# top.net
KiCad netlist of a schematic drawn in Altium Designer
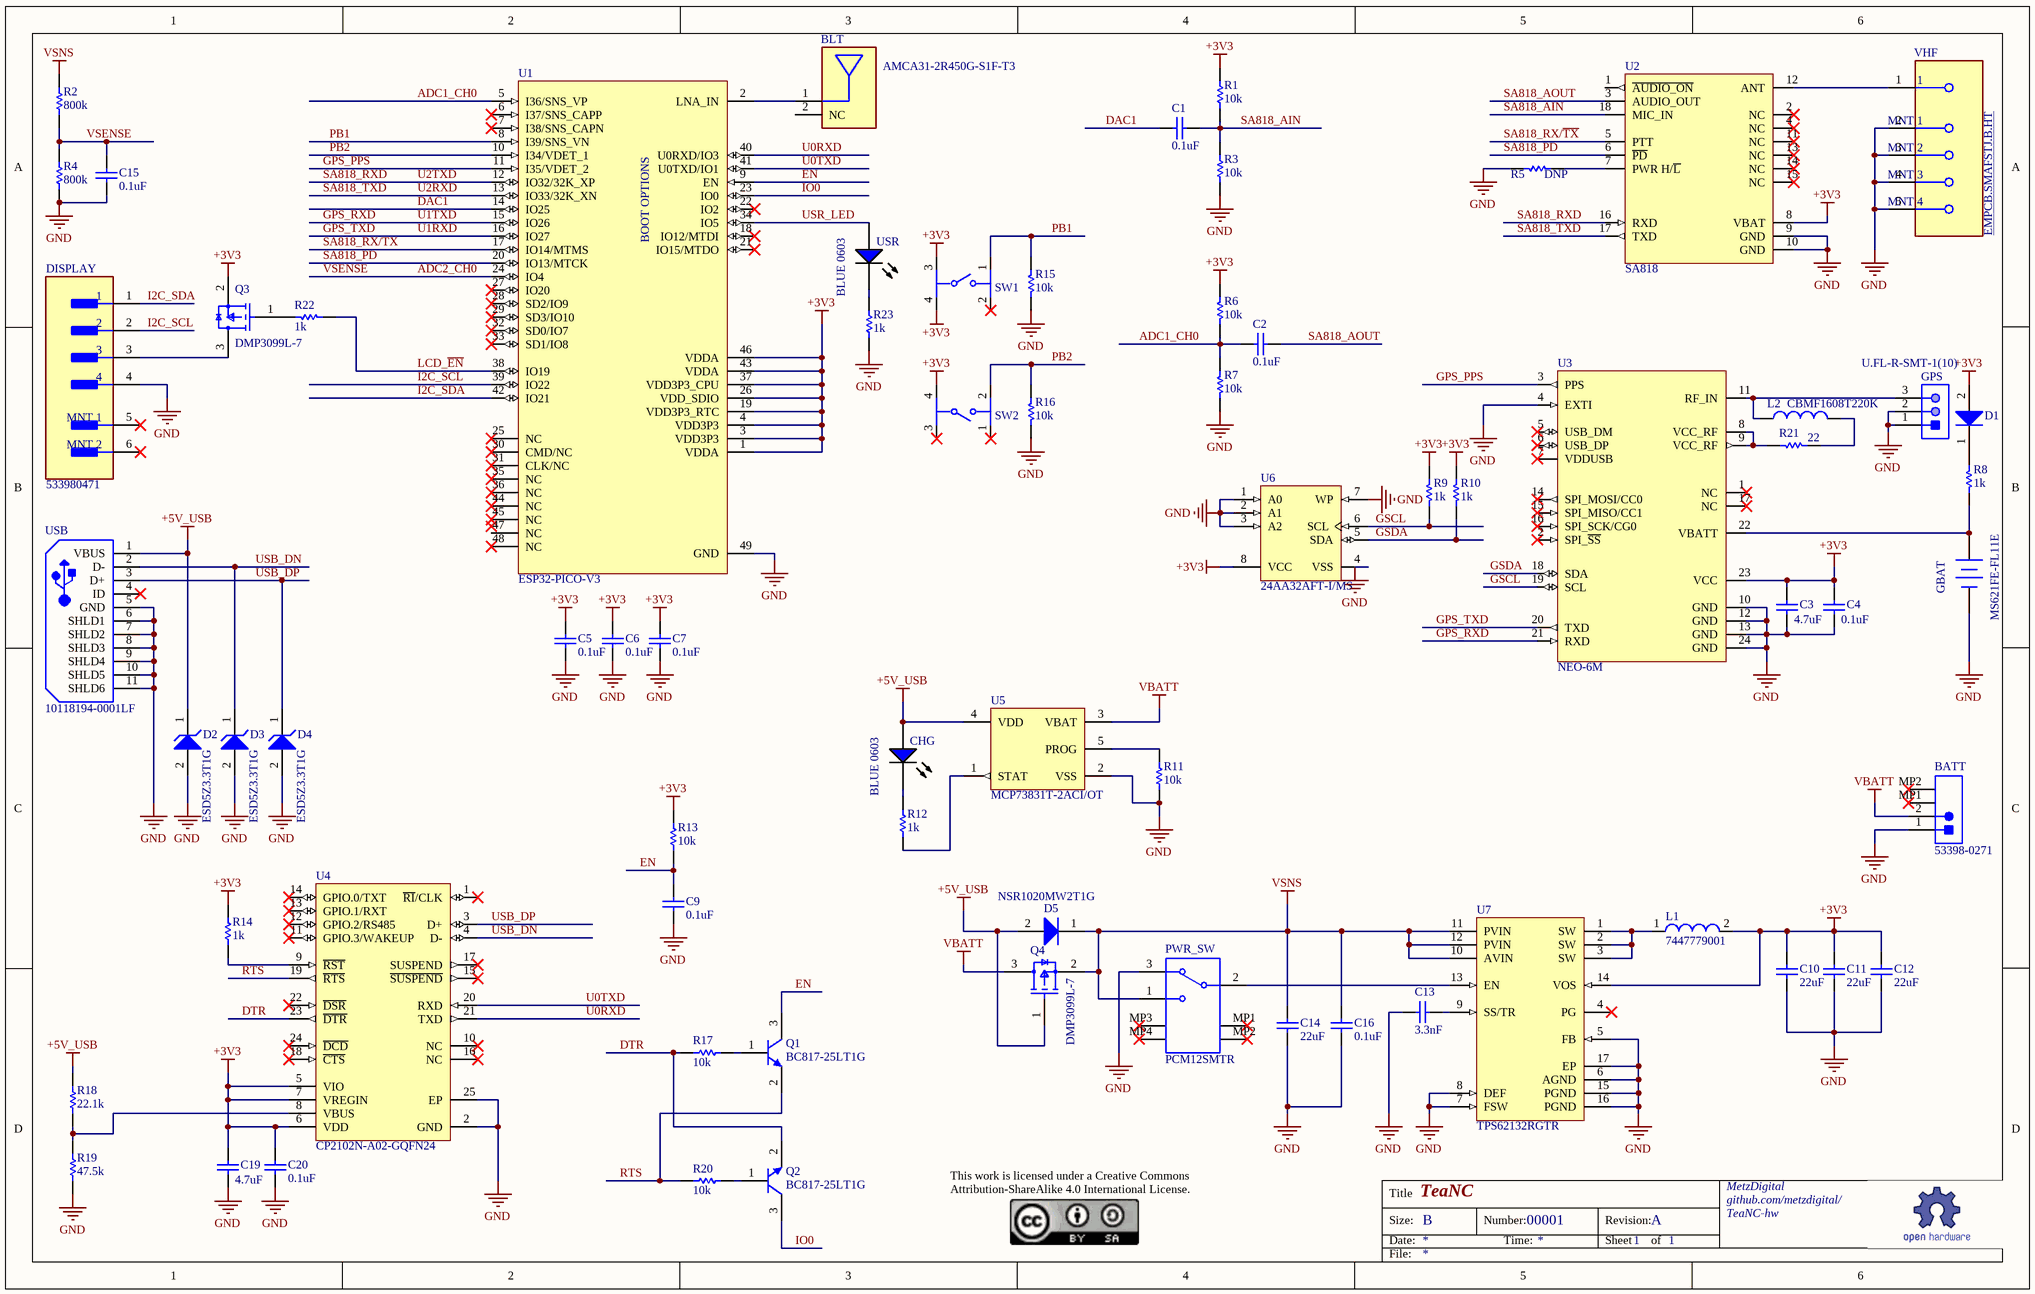
[diagram p0: top.SchDoc]

(export (version "E")
  (design (tool "Eeschema 10.0.6"))
  (components
    (comp (ref "BATT")
      (value "53398-0271")
      (footprint "MOLX-53398-0271_V")
      (description "Male Header, Pitch 1.25 mm, 1 x 2 Position, Height 4.7 mm, -40 to 85 degC, RoHS, Tape and Reel")
      (fields (field (name "MANUFACTURER") "Molex"))
      (libsource (lib "Altium Content Vault") (part "CN-1P-2M-R2"))
    )
    (comp (ref "BLT")
      (value "AMCA31-2R450G-S1F-T3")
      (footprint "FP-AMCA31-MFG")
      (description "RF ANT 2.4GHZ CHIP SOLDER SMD")
      (fields
        (field (name "OCTOPART") "https://octopart.com/amca31-2r450g-s1f-t3-abracon-31435383")
        (field (name "MANUFACTURER") "Abracon")
      )
      (libsource (lib "Altium Content Vault") (part "feefd54aed95757a858c12fc87bd8d5"))
    )
    (comp (ref "C1")
      (value "0.1uF")
      (footprint "CAPC0603(1608)100_M")
      (description "CAP 100nF 50V ±20% 0603 (1608 Metric) Thickness 1mm SMD")
      (fields (field (name "TOLERANCE") "Â±20%"))
      (libsource (lib "Altium Content Vault") (part "CMP-1035-02593-1"))
    )
    (comp (ref "C2")
      (value "0.1uF")
      (footprint "CAPC0603(1608)100_M")
      (description "CAP 100nF 50V ±20% 0603 (1608 Metric) Thickness 1mm SMD")
      (fields (field (name "TOLERANCE") "Â±20%"))
      (libsource (lib "Altium Content Vault") (part "CMP-1035-02593-1"))
    )
    (comp (ref "C3")
      (value "4.7uF")
      (footprint "CAPC0603(1608)100_M")
      (description "CAP 100nF 50V ±20% 0603 (1608 Metric) Thickness 1mm SMD")
      (fields (field (name "TOLERANCE") "Â±20%"))
      (libsource (lib "Altium Content Vault") (part "CMP-1035-02593-1"))
    )
    (comp (ref "C4")
      (value "0.1uF")
      (footprint "CAPC0603(1608)100_M")
      (description "CAP 100nF 50V ±20% 0603 (1608 Metric) Thickness 1mm SMD")
      (fields (field (name "TOLERANCE") "Â±20%"))
      (libsource (lib "Altium Content Vault") (part "CMP-1035-02593-1"))
    )
    (comp (ref "C5")
      (value "0.1uF")
      (footprint "CAPC0603(1608)100_M")
      (description "CAP 100nF 50V ±20% 0603 (1608 Metric) Thickness 1mm SMD")
      (fields (field (name "TOLERANCE") "Â±20%"))
      (libsource (lib "Altium Content Vault") (part "CMP-1035-02593-1"))
    )
    (comp (ref "C6")
      (value "0.1uF")
      (footprint "CAPC0603(1608)100_M")
      (description "CAP 100nF 50V ±20% 0603 (1608 Metric) Thickness 1mm SMD")
      (fields (field (name "TOLERANCE") "Â±20%"))
      (libsource (lib "Altium Content Vault") (part "CMP-1035-02593-1"))
    )
    (comp (ref "C7")
      (value "0.1uF")
      (footprint "CAPC0603(1608)100_M")
      (description "CAP 100nF 50V ±20% 0603 (1608 Metric) Thickness 1mm SMD")
      (fields (field (name "TOLERANCE") "Â±20%"))
      (libsource (lib "Altium Content Vault") (part "CMP-1035-02593-1"))
    )
    (comp (ref "C9")
      (value "0.1uF")
      (footprint "CAPC0603(1608)100_M")
      (description "CAP 100nF 50V ±20% 0603 (1608 Metric) Thickness 1mm SMD")
      (fields (field (name "TOLERANCE") "Â±20%"))
      (libsource (lib "Altium Content Vault") (part "CMP-1035-02593-1"))
    )
    (comp (ref "C10")
      (value "22uF")
      (footprint "CAPC1206(3216)190_M")
      (description "CAP 1uF 100V ±10% 1206 (3216 Metric) Thickness 1.9mm SMD")
      (fields (field (name "TOLERANCE") "Â±10%"))
      (libsource (lib "Altium Content Vault") (part "CAP"))
    )
    (comp (ref "C11")
      (value "22uF")
      (footprint "CAPC1206(3216)190_M")
      (description "CAP 1uF 100V ±10% 1206 (3216 Metric) Thickness 1.9mm SMD")
      (fields (field (name "TOLERANCE") "Â±10%"))
      (libsource (lib "Altium Content Vault") (part "CAP"))
    )
    (comp (ref "C12")
      (value "22uF")
      (footprint "CAPC1206(3216)190_M")
      (description "CAP 1uF 100V ±10% 1206 (3216 Metric) Thickness 1.9mm SMD")
      (fields (field (name "TOLERANCE") "Â±10%"))
      (libsource (lib "Altium Content Vault") (part "CAP"))
    )
    (comp (ref "C13")
      (value "3.3nF")
      (footprint "CAPC0603(1608)100_M")
      (description "CAP 100nF 50V ±20% 0603 (1608 Metric) Thickness 1mm SMD")
      (fields (field (name "TOLERANCE") "Â±20%"))
      (libsource (lib "Altium Content Vault") (part "CMP-1035-02593-1"))
    )
    (comp (ref "C14")
      (value "22uF")
      (footprint "CAPC1206(3216)190_M")
      (description "CAP 1uF 100V ±10% 1206 (3216 Metric) Thickness 1.9mm SMD")
      (fields (field (name "TOLERANCE") "Â±10%"))
      (libsource (lib "Altium Content Vault") (part "CAP"))
    )
    (comp (ref "C15")
      (value "0.1uF")
      (footprint "CAPC0603(1608)100_M")
      (description "CAP 100nF 50V ±20% 0603 (1608 Metric) Thickness 1mm SMD")
      (fields (field (name "TOLERANCE") "Â±20%"))
      (libsource (lib "Altium Content Vault") (part "CMP-1035-02593-1"))
    )
    (comp (ref "C16")
      (value "0.1uF")
      (footprint "CAPC0603(1608)100_M")
      (description "CAP 100nF 50V ±20% 0603 (1608 Metric) Thickness 1mm SMD")
      (fields (field (name "TOLERANCE") "Â±20%"))
      (libsource (lib "Altium Content Vault") (part "CMP-1035-02593-1"))
    )
    (comp (ref "C19")
      (value "4.7uF")
      (footprint "CAPC0603(1608)100_M")
      (description "CAP 100nF 50V ±20% 0603 (1608 Metric) Thickness 1mm SMD")
      (fields (field (name "TOLERANCE") "Â±20%"))
      (libsource (lib "Altium Content Vault") (part "CMP-1035-02593-1"))
    )
    (comp (ref "C20")
      (value "0.1uF")
      (footprint "CAPC0603(1608)100_M")
      (description "CAP 100nF 50V ±20% 0603 (1608 Metric) Thickness 1mm SMD")
      (fields (field (name "TOLERANCE") "Â±20%"))
      (libsource (lib "Altium Content Vault") (part "CMP-1035-02593-1"))
    )
    (comp (ref "CHG")
      (value "BLUE 0603")
      (footprint "VISH-TLMX1100-2_V")
      (description "Blue LED, 10 mA, 3.9 V, -40 to 100 degC, 2-Pin SMD (0603), RoHS, Tape and Reel")
      (fields (field (name "TOLERANCE") "10%"))
      (libsource (lib "Altium Content Vault") (part "LED-BLUE-AK-2"))
    )
    (comp (ref "D1")
      (value "NSR1020MW2T1G")
      (footprint "ONSC-SOD-323-2-477-02_V")
      (description "Schottky Barrier Diode, 2-Pin SOD-323, Pb-Free, Tape and Reel")
      (fields (field (name "MANUFACTURER") "On Semiconductor"))
      (libsource (lib "Altium Content Vault") (part "ONSC-D-K1A2-2"))
    )
    (comp (ref "D2")
      (value "ESD5Z3.3T1G")
      (footprint "ONSC-SOD-523-2-502-01_V")
      (fields (field (name "MANUFACTURER") "On Semiconductor"))
      (libsource (lib "Altium Content Vault") (part "ONSC-K1A2-2"))
    )
    (comp (ref "D3")
      (value "ESD5Z3.3T1G")
      (footprint "ONSC-SOD-523-2-502-01_V")
      (fields (field (name "MANUFACTURER") "On Semiconductor"))
      (libsource (lib "Altium Content Vault") (part "ONSC-K1A2-2"))
    )
    (comp (ref "D4")
      (value "ESD5Z3.3T1G")
      (footprint "ONSC-SOD-523-2-502-01_V")
      (fields (field (name "MANUFACTURER") "On Semiconductor"))
      (libsource (lib "Altium Content Vault") (part "ONSC-K1A2-2"))
    )
    (comp (ref "D5")
      (value "NSR1020MW2T1G")
      (footprint "ONSC-SOD-323-2-477-02_V")
      (description "Schottky Barrier Diode, 2-Pin SOD-323, Pb-Free, Tape and Reel")
      (fields (field (name "MANUFACTURER") "On Semiconductor"))
      (libsource (lib "Altium Content Vault") (part "ONSC-D-K1A2-2"))
    )
    (comp (ref "DISPLAY")
      (value "533980471")
      (footprint "FP-533980471-MFG")
      (description "CONN HEADER SMD 4POS 1.25MM")
      (fields
        (field (name "OCTOPART") "https://octopart.com/53398-0471-molex-655296")
        (field (name "MANUFACTURER") "Molex")
      )
      (libsource (lib "Altium Content Vault") (part "3b6f738a5616415d78381ad43816e4a"))
    )
    (comp (ref "GBAT")
      (value "MS621FE-FL11E")
      (footprint "SEIK-MS621FE-FL11E-2_V")
      (description "MS Lihium Rechargeable Battery, 3 V, -20 to 60 degC, Tray")
      (fields (field (name "MANUFACTURER") "SeikoInstruments"))
      (libsource (lib "Altium Content Vault") (part "BATTERY_SINGLE-2"))
    )
    (comp (ref "GPS")
      (value "U.FL-R-SMT-1(10)")
      (footprint "HRS-U.FL-R-SMT-1(10)_V")
      (description "Ultra Small Surface Mount Coaxial Connector, -40 to 90 degC, 2-Pin SMT, RoHS, Tape and Reel")
      (fields (field (name "MANUFACTURER") "Hirose Electric"))
      (libsource (lib "Altium Content Vault") (part "CN-1P-M-R3"))
    )
    (comp (ref "L1")
      (value "7447779001")
      (footprint "WE-PD-M-PB")
      (description "SMD-Shielded Power Inductor WE-PD, L = 1.00 µH")
      (libsource (lib "Altium Content Vault") (part "PAS-IND-INDUCTOR-2"))
    )
    (comp (ref "L2")
      (value "CBMF1608T220K")
      (footprint "INDC1608X90X30LL10T20")
      (fields (field (name "MANUFACTURER") "EPCOS-(TDK)") (field (name "TOLERANCE") "±5%"))
      (libsource (lib "Altium Content Vault") (part "IND-2"))
    )
    (comp (ref "PWR_SW")
      (value "PCM12SMTR")
      (footprint "CKCP-PCM12SMTR_V")
      (description "Ultraminiature Slide Switch, SPDT, 0.3 A, 6 V, -20 to 85 degC, 3-Pin SMD, RoHS, Tape and Reel")
      (fields (field (name "MANUFACTURER") "C&K Components"))
      (libsource (lib "Altium Content Vault") (part "SW-SPDT-3_A"))
    )
    (comp (ref "Q1")
      (value "BC817-25LT1G")
      (footprint "ONSC-SOT-23-3-318-08_V")
      (description "General Purpose Transistor, NPN Silicon, 3-Pin SOT-23, Pb-Free, Tape and Reel")
      (fields (field (name "MANUFACTURER") "On Semiconductor"))
      (libsource (lib "Altium Content Vault") (part "ONSC-NPN-B1E2C3-3"))
    )
    (comp (ref "Q2")
      (value "BC817-25LT1G")
      (footprint "ONSC-SOT-23-3-318-08_V")
      (description "General Purpose Transistor, NPN Silicon, 3-Pin SOT-23, Pb-Free, Tape and Reel")
      (fields (field (name "MANUFACTURER") "On Semiconductor"))
      (libsource (lib "Altium Content Vault") (part "ONSC-NPN-B1E2C3-3"))
    )
    (comp (ref "Q3")
      (value "DMP3099L-7")
      (footprint "FP-SOT23-MFG")
      (description "MOSFET P-CH 30V SOT23")
      (fields
        (field (name "MANUFACTURER") "Diodes Inc.")
        (field (name "OCTOPART") "https://octopart.com/dmp3099l-7-diodes+inc.-30954908")
      )
      (libsource (lib "Altium Content Vault") (part "3e7659e92714c59366284b818339c1c"))
    )
    (comp (ref "Q4")
      (value "DMP3099L-7")
      (footprint "FP-SOT23-MFG")
      (description "MOSFET P-CH 30V SOT23")
      (fields
        (field (name "MANUFACTURER") "Diodes Inc.")
        (field (name "OCTOPART") "https://octopart.com/dmp3099l-7-diodes+inc.-30954908")
      )
      (libsource (lib "Altium Content Vault") (part "3e7659e92714c59366284b818339c1c"))
    )
    (comp (ref "R1")
      (value "10k")
      (footprint "RESC1609X55X30LL15T15")
      (description "Chip Resistor, 10 KOhm, +/- 1%, 0.1 W, -55 to 155 degC, 0603 (1608 Metric), RoHS, Tape and Reel")
      (fields (field (name "TOLERANCE") "1%") (field (name "MANUFACTURER") "Panasonic"))
      (libsource (lib "Altium Content Vault") (part "RES-2"))
    )
    (comp (ref "R2")
      (value "800k")
      (footprint "RESC1609X55X30LL15T15")
      (description "Chip Resistor, 10 KOhm, +/- 1%, 0.1 W, -55 to 155 degC, 0603 (1608 Metric), RoHS, Tape and Reel")
      (fields (field (name "TOLERANCE") "1%") (field (name "MANUFACTURER") "Panasonic"))
      (libsource (lib "Altium Content Vault") (part "RES-2"))
    )
    (comp (ref "R3")
      (value "10k")
      (footprint "RESC1609X55X30LL15T15")
      (description "Chip Resistor, 10 KOhm, +/- 1%, 0.1 W, -55 to 155 degC, 0603 (1608 Metric), RoHS, Tape and Reel")
      (fields (field (name "TOLERANCE") "1%") (field (name "MANUFACTURER") "Panasonic"))
      (libsource (lib "Altium Content Vault") (part "RES-2"))
    )
    (comp (ref "R4")
      (value "800k")
      (footprint "RESC1609X55X30LL15T15")
      (description "Chip Resistor, 10 KOhm, +/- 1%, 0.1 W, -55 to 155 degC, 0603 (1608 Metric), RoHS, Tape and Reel")
      (fields (field (name "TOLERANCE") "1%") (field (name "MANUFACTURER") "Panasonic"))
      (libsource (lib "Altium Content Vault") (part "RES-2"))
    )
    (comp (ref "R5")
      (value "DNP")
      (footprint "RESC1609X55X30LL15T15")
      (description "Chip Resistor, 10 KOhm, +/- 1%, 0.1 W, -55 to 155 degC, 0603 (1608 Metric), RoHS, Tape and Reel")
      (fields (field (name "TOLERANCE") "1%") (field (name "MANUFACTURER") "Panasonic"))
      (libsource (lib "Altium Content Vault") (part "RES-2"))
    )
    (comp (ref "R6")
      (value "10k")
      (footprint "RESC1609X55X30LL15T15")
      (description "Chip Resistor, 10 KOhm, +/- 1%, 0.1 W, -55 to 155 degC, 0603 (1608 Metric), RoHS, Tape and Reel")
      (fields (field (name "TOLERANCE") "1%") (field (name "MANUFACTURER") "Panasonic"))
      (libsource (lib "Altium Content Vault") (part "RES-2"))
    )
    (comp (ref "R7")
      (value "10k")
      (footprint "RESC1609X55X30LL15T15")
      (description "Chip Resistor, 10 KOhm, +/- 1%, 0.1 W, -55 to 155 degC, 0603 (1608 Metric), RoHS, Tape and Reel")
      (fields (field (name "TOLERANCE") "1%") (field (name "MANUFACTURER") "Panasonic"))
      (libsource (lib "Altium Content Vault") (part "RES-2"))
    )
    (comp (ref "R8")
      (value "1k")
      (footprint "RESC1609X55X30LL15T15")
      (description "Chip Resistor, 10 KOhm, +/- 1%, 0.1 W, -55 to 155 degC, 0603 (1608 Metric), RoHS, Tape and Reel")
      (fields (field (name "TOLERANCE") "1%") (field (name "MANUFACTURER") "Panasonic"))
      (libsource (lib "Altium Content Vault") (part "RES-2"))
    )
    (comp (ref "R9")
      (value "1k")
      (footprint "RESC1609X55X30LL15T15")
      (description "Chip Resistor, 10 KOhm, +/- 1%, 0.1 W, -55 to 155 degC, 0603 (1608 Metric), RoHS, Tape and Reel")
      (fields (field (name "TOLERANCE") "1%") (field (name "MANUFACTURER") "Panasonic"))
      (libsource (lib "Altium Content Vault") (part "RES-2"))
    )
    (comp (ref "R10")
      (value "1k")
      (footprint "RESC1609X55X30LL15T15")
      (description "Chip Resistor, 10 KOhm, +/- 1%, 0.1 W, -55 to 155 degC, 0603 (1608 Metric), RoHS, Tape and Reel")
      (fields (field (name "TOLERANCE") "1%") (field (name "MANUFACTURER") "Panasonic"))
      (libsource (lib "Altium Content Vault") (part "RES-2"))
    )
    (comp (ref "R11")
      (value "10k")
      (footprint "RESC1609X55X30LL15T15")
      (description "Chip Resistor, 10 KOhm, +/- 1%, 0.1 W, -55 to 155 degC, 0603 (1608 Metric), RoHS, Tape and Reel")
      (fields (field (name "TOLERANCE") "1%") (field (name "MANUFACTURER") "Panasonic"))
      (libsource (lib "Altium Content Vault") (part "RES-2"))
    )
    (comp (ref "R12")
      (value "1k")
      (footprint "RESC1609X55X30LL15T15")
      (description "Chip Resistor, 10 KOhm, +/- 1%, 0.1 W, -55 to 155 degC, 0603 (1608 Metric), RoHS, Tape and Reel")
      (fields (field (name "TOLERANCE") "1%") (field (name "MANUFACTURER") "Panasonic"))
      (libsource (lib "Altium Content Vault") (part "RES-2"))
    )
    (comp (ref "R13")
      (value "10k")
      (footprint "RESC1609X55X30LL15T15")
      (description "Chip Resistor, 10 KOhm, +/- 1%, 0.1 W, -55 to 155 degC, 0603 (1608 Metric), RoHS, Tape and Reel")
      (fields (field (name "TOLERANCE") "1%") (field (name "MANUFACTURER") "Panasonic"))
      (libsource (lib "Altium Content Vault") (part "RES-2"))
    )
    (comp (ref "R14")
      (value "1k")
      (footprint "RESC1609X55X30LL15T15")
      (description "Chip Resistor, 10 KOhm, +/- 1%, 0.1 W, -55 to 155 degC, 0603 (1608 Metric), RoHS, Tape and Reel")
      (fields (field (name "TOLERANCE") "1%") (field (name "MANUFACTURER") "Panasonic"))
      (libsource (lib "Altium Content Vault") (part "RES-2"))
    )
    (comp (ref "R15")
      (value "10k")
      (footprint "RESC1609X55X30LL15T15")
      (description "Chip Resistor, 10 KOhm, +/- 1%, 0.1 W, -55 to 155 degC, 0603 (1608 Metric), RoHS, Tape and Reel")
      (fields (field (name "TOLERANCE") "1%") (field (name "MANUFACTURER") "Panasonic"))
      (libsource (lib "Altium Content Vault") (part "RES-2"))
    )
    (comp (ref "R16")
      (value "10k")
      (footprint "RESC1609X55X30LL15T15")
      (description "Chip Resistor, 10 KOhm, +/- 1%, 0.1 W, -55 to 155 degC, 0603 (1608 Metric), RoHS, Tape and Reel")
      (fields (field (name "TOLERANCE") "1%") (field (name "MANUFACTURER") "Panasonic"))
      (libsource (lib "Altium Content Vault") (part "RES-2"))
    )
    (comp (ref "R17")
      (value "10k")
      (footprint "RESC1609X55X30LL15T15")
      (description "Chip Resistor, 10 KOhm, +/- 1%, 0.1 W, -55 to 155 degC, 0603 (1608 Metric), RoHS, Tape and Reel")
      (fields (field (name "TOLERANCE") "1%") (field (name "MANUFACTURER") "Panasonic"))
      (libsource (lib "Altium Content Vault") (part "RES-2"))
    )
    (comp (ref "R18")
      (value "22.1k")
      (footprint "RESC1609X55X30LL15T15")
      (description "Chip Resistor, 10 KOhm, +/- 1%, 0.1 W, -55 to 155 degC, 0603 (1608 Metric), RoHS, Tape and Reel")
      (fields (field (name "TOLERANCE") "1%") (field (name "MANUFACTURER") "Panasonic"))
      (libsource (lib "Altium Content Vault") (part "RES-2"))
    )
    (comp (ref "R19")
      (value "47.5k")
      (footprint "RESC1609X55X30LL15T15")
      (description "Chip Resistor, 10 KOhm, +/- 1%, 0.1 W, -55 to 155 degC, 0603 (1608 Metric), RoHS, Tape and Reel")
      (fields (field (name "TOLERANCE") "1%") (field (name "MANUFACTURER") "Panasonic"))
      (libsource (lib "Altium Content Vault") (part "RES-2"))
    )
    (comp (ref "R20")
      (value "10k")
      (footprint "RESC1609X55X30LL15T15")
      (description "Chip Resistor, 10 KOhm, +/- 1%, 0.1 W, -55 to 155 degC, 0603 (1608 Metric), RoHS, Tape and Reel")
      (fields (field (name "TOLERANCE") "1%") (field (name "MANUFACTURER") "Panasonic"))
      (libsource (lib "Altium Content Vault") (part "RES-2"))
    )
    (comp (ref "R21")
      (value "22")
      (footprint "RESC1609X55X30LL15T15")
      (description "Chip Resistor, 10 KOhm, +/- 1%, 0.1 W, -55 to 155 degC, 0603 (1608 Metric), RoHS, Tape and Reel")
      (fields (field (name "TOLERANCE") "1%") (field (name "MANUFACTURER") "Panasonic"))
      (libsource (lib "Altium Content Vault") (part "RES-2"))
    )
    (comp (ref "R22")
      (value "1k")
      (footprint "RESC1609X55X30LL15T15")
      (description "Chip Resistor, 10 KOhm, +/- 1%, 0.1 W, -55 to 155 degC, 0603 (1608 Metric), RoHS, Tape and Reel")
      (fields (field (name "TOLERANCE") "1%") (field (name "MANUFACTURER") "Panasonic"))
      (libsource (lib "Altium Content Vault") (part "RES-2"))
    )
    (comp (ref "R23")
      (value "1k")
      (footprint "RESC1609X55X30LL15T15")
      (description "Chip Resistor, 10 KOhm, +/- 1%, 0.1 W, -55 to 155 degC, 0603 (1608 Metric), RoHS, Tape and Reel")
      (fields (field (name "TOLERANCE") "1%") (field (name "MANUFACTURER") "Panasonic"))
      (libsource (lib "Altium Content Vault") (part "RES-2"))
    )
    (comp (ref "SW1")
      (value "PTS840 GKP SMTR LFS")
      (footprint "FP-PTS840_GKP_SMTR_LFS-MFG")
      (description "SWITCH TACTILE SPST-NO 0.05A 12V")
      (fields
        (field (name "MANUFACTURER") "C&K Components")
        (field (name "OCTOPART") "https://octopart.com/pts840gkpsmtrlfs-c%26k+components-29380303")
      )
      (libsource (lib "Altium Content Vault") (part "1adf0dd01260c80cf25a44bfd6b99ba"))
    )
    (comp (ref "SW2")
      (value "PTS840 GKP SMTR LFS")
      (footprint "FP-PTS840_GKP_SMTR_LFS-MFG")
      (description "SWITCH TACTILE SPST-NO 0.05A 12V")
      (fields
        (field (name "MANUFACTURER") "C&K Components")
        (field (name "OCTOPART") "https://octopart.com/pts840gkpsmtrlfs-c%26k+components-29380303")
      )
      (libsource (lib "Altium Content Vault") (part "1adf0dd01260c80cf25a44bfd6b99ba"))
    )
    (comp (ref "U1")
      (value "ESP32-PICO-V3")
      (footprint "QFN_M 48 POS")
      (description "ESP32 WIFI BLUETOOTH MCU")
      (libsource (lib "JPLLib") (part "ESP32-PICO-V3"))
    )
    (comp (ref "U2")
      (value "SA818")
      (footprint "SA818")
      (description "1W Embedded Small Size Walkie Talkie")
      (libsource (lib "Schlib1") (part "SA818"))
    )
    (comp (ref "U3")
      (value "NEO-6M")
      (footprint "NEO-6M")
      (description "NEO-6 series of GPS module")
      (libsource (lib "Schlib1") (part "NEO-6M"))
    )
    (comp (ref "U4")
      (value "CP2102N-A02-GQFN24")
      (footprint "SLAB-QFN-24-2550x2550TP_A_V")
      (description "USBXpress(TM) Family, 4 GPIOs, 2.2 to 3.6 V, -40 to 85 degC, 24-Pin QFN, RoHS")
      (fields (field (name "MANUFACTURER") "Silicon Labs"))
      (libsource (lib "Altium Content Vault") (part "SLAB-CP2102N-QFN-24"))
    )
    (comp (ref "U5")
      (value "MCP73831T-2ACI/OT")
      (footprint "SOT-23-OT5_M")
      (libsource (lib "Altium Content Vault") (part "PM-BM-MCP73831-SOT5"))
    )
    (comp (ref "U6")
      (value "24AA32AFT-I/MS")
      (footprint "MSOP-MS8_N")
      (libsource (lib "Altium Content Vault") (part "MEM-SEEPROM-34AA02-IL8"))
    )
    (comp (ref "U7")
      (value "TPS62132RGTR")
      (footprint "RGT0016C_V")
      (fields (field (name "MANUFACTURER") "Texas Instruments"))
      (libsource (lib "Altium Content Vault") (part "TI-TPS62132RGT16-1700X1700TP"))
    )
    (comp (ref "USB")
      (value "10118194-0001LF")
      (footprint "FCI-10118194-0001LF-5_V")
      (description "Micro USB B Type Receptacle, 1.8 A, -55 to 85 degC, 5-Pin SMD, RoHS, Tape and Reel")
      (fields (field (name "MANUFACTURER") "Amphenol FCI"))
      (libsource (lib "Altium Content Vault") (part "USB-5-6SHLD"))
    )
    (comp (ref "USR")
      (value "BLUE 0603")
      (footprint "VISH-TLMX1100-2_V")
      (description "Blue LED, 10 mA, 3.9 V, -40 to 100 degC, 2-Pin SMD (0603), RoHS, Tape and Reel")
      (fields (field (name "TOLERANCE") "10%"))
      (libsource (lib "Altium Content Vault") (part "LED-BLUE-AK-2"))
    )
    (comp (ref "VHF")
      (value "EMPCB.SMAFSTJ.B.HT")
      (footprint "FP-EMPCB_SMAFSTJ_B_HT-MFG")
      (description "CONN SMA JACK STR 50OHM EDGE MNT")
      (fields
        (field (name "OCTOPART") "https://octopart.com/empcb.smafstj.b.ht-taoglas-24204431")
        (field (name "MANUFACTURER") "Taoglas Limited")
      )
      (libsource (lib "Altium Content Vault") (part "c65b8a639cdaef1819ea20b5466f8fa"))
    )
  )
  (nets
    (net (code "1") (name "+3V3") (class "Default")
      (node (ref "C10") (pin "2") (pinfunction "2_2") (pintype "passive"))
      (node (ref "C11") (pin "2") (pinfunction "2_2") (pintype "passive"))
      (node (ref "C12") (pin "2") (pinfunction "2_2") (pintype "passive"))
      (node (ref "C19") (pin "2") (pinfunction "2_2") (pintype "passive"))
      (node (ref "C20") (pin "2") (pinfunction "2_2") (pintype "passive"))
      (node (ref "C3") (pin "2") (pinfunction "2_2") (pintype "passive"))
      (node (ref "C4") (pin "2") (pinfunction "2_2") (pintype "passive"))
      (node (ref "C5") (pin "2") (pinfunction "2_2") (pintype "passive"))
      (node (ref "C6") (pin "2") (pinfunction "2_2") (pintype "passive"))
      (node (ref "C7") (pin "2") (pinfunction "2_2") (pintype "passive"))
      (node (ref "D1") (pin "2") (pinfunction "A_2") (pintype "passive"))
      (node (ref "L1") (pin "2") (pinfunction "2_2") (pintype "passive"))
      (node (ref "Q3") (pin "2") (pinfunction "SOURCE_2") (pintype "passive"))
      (node (ref "R1") (pin "2") (pinfunction "2_2") (pintype "passive"))
      (node (ref "R10") (pin "2") (pinfunction "2_2") (pintype "passive"))
      (node (ref "R13") (pin "1") (pinfunction "1_1") (pintype "passive"))
      (node (ref "R14") (pin "1") (pinfunction "1_1") (pintype "passive"))
      (node (ref "R6") (pin "2") (pinfunction "2_2") (pintype "passive"))
      (node (ref "R9") (pin "2") (pinfunction "2_2") (pintype "passive"))
      (node (ref "SW1") (pin "3") (pinfunction "3_3") (pintype "passive"))
      (node (ref "SW1") (pin "4") (pinfunction "4_4") (pintype "passive"))
      (node (ref "SW2") (pin "4") (pinfunction "4_4") (pintype "passive"))
      (node (ref "U1") (pin "1") (pinfunction "VDDA_1") (pintype "passive"))
      (node (ref "U1") (pin "19") (pinfunction "VDD3P3_RTC_19") (pintype "passive"))
      (node (ref "U1") (pin "26") (pinfunction "VDD_SDIO_26") (pintype "passive"))
      (node (ref "U1") (pin "3") (pinfunction "VDD3P3_3") (pintype "passive"))
      (node (ref "U1") (pin "37") (pinfunction "VDD3P3_CPU_37") (pintype "passive"))
      (node (ref "U1") (pin "4") (pinfunction "VDD3P3_4") (pintype "passive"))
      (node (ref "U1") (pin "43") (pinfunction "VDDA_43") (pintype "passive"))
      (node (ref "U1") (pin "46") (pinfunction "VDDA_46") (pintype "passive"))
      (node (ref "U2") (pin "8") (pinfunction "VBAT_8") (pintype "passive"))
      (node (ref "U3") (pin "23") (pinfunction "VCC_23") (pintype "passive"))
      (node (ref "U4") (pin "5") (pinfunction "VIO_5") (pintype "power_in"))
      (node (ref "U4") (pin "6") (pinfunction "VDD_6") (pintype "power_in"))
      (node (ref "U4") (pin "7") (pinfunction "VREGIN_7") (pintype "power_in"))
      (node (ref "U6") (pin "8") (pinfunction "VCC_8") (pintype "power_in"))
      (node (ref "U7") (pin "14") (pinfunction "VOS_14") (pintype "input"))
    )
    (net (code "2") (name "+5V_USB") (class "Default")
      (node (ref "CHG") (pin "1") (pinfunction "A_1") (pintype "passive"))
      (node (ref "D2") (pin "1") (pinfunction "K_1") (pintype "passive"))
      (node (ref "D5") (pin "2") (pinfunction "A_2") (pintype "passive"))
      (node (ref "Q4") (pin "1") (pinfunction "GATE_1") (pintype "passive"))
      (node (ref "R18") (pin "1") (pinfunction "1_1") (pintype "passive"))
      (node (ref "U5") (pin "4") (pinfunction "VDD_4") (pintype "power_in"))
      (node (ref "USB") (pin "1") (pinfunction "VBUS_1") (pintype "passive"))
    )
    (net (code "3") (name "/ADC1_CH0") (class "Default")
      (node (ref "C2") (pin "1") (pinfunction "1_1") (pintype "passive"))
      (node (ref "R6") (pin "1") (pinfunction "1_1") (pintype "passive"))
      (node (ref "R7") (pin "2") (pinfunction "2_2") (pintype "passive"))
      (node (ref "U1") (pin "5") (pinfunction "I36/SNS_VP_5") (pintype "input"))
    )
    (net (code "4") (name "/ADC2_CH0") (class "Default")
      (node (ref "C15") (pin "2") (pinfunction "2_2") (pintype "passive"))
      (node (ref "R2") (pin "1") (pinfunction "1_1") (pintype "passive"))
      (node (ref "R4") (pin "2") (pinfunction "2_2") (pintype "passive"))
      (node (ref "U1") (pin "24") (pinfunction "IO4_24") (pintype "bidirectional"))
    )
    (net (code "5") (name "/DAC1") (class "Default")
      (node (ref "C1") (pin "2") (pinfunction "2_2") (pintype "passive"))
      (node (ref "U1") (pin "14") (pinfunction "IO25_14") (pintype "bidirectional"))
    )
    (net (code "6") (name "/DTR") (class "Default")
      (node (ref "Q2") (pin "2") (pinfunction "E_2") (pintype "passive"))
      (node (ref "R17") (pin "2") (pinfunction "2_2") (pintype "passive"))
      (node (ref "U4") (pin "23") (pinfunction "~{DTR}_23") (pintype "output"))
    )
    (net (code "7") (name "/EN") (class "Default")
      (node (ref "C9") (pin "2") (pinfunction "2_2") (pintype "passive"))
      (node (ref "Q1") (pin "3") (pinfunction "C_3") (pintype "passive"))
      (node (ref "R13") (pin "2") (pinfunction "2_2") (pintype "passive"))
      (node (ref "U1") (pin "9") (pinfunction "EN_9") (pintype "input"))
    )
    (net (code "8") (name "/GPS_PPS") (class "Default")
      (node (ref "U1") (pin "11") (pinfunction "I35/VDET_2_11") (pintype "input"))
      (node (ref "U3") (pin "3") (pinfunction "PPS_3") (pintype "output"))
    )
    (net (code "9") (name "/GPS_RXD") (class "Default")
      (node (ref "U1") (pin "15") (pinfunction "IO26_15") (pintype "bidirectional"))
      (node (ref "U3") (pin "21") (pinfunction "RXD_21") (pintype "input"))
    )
    (net (code "10") (name "/GPS_TXD") (class "Default")
      (node (ref "U1") (pin "16") (pinfunction "IO27_16") (pintype "bidirectional"))
      (node (ref "U3") (pin "20") (pinfunction "TXD_20") (pintype "output"))
    )
    (net (code "11") (name "/GSCL") (class "Default")
      (node (ref "R9") (pin "1") (pinfunction "1_1") (pintype "passive"))
      (node (ref "U3") (pin "19") (pinfunction "SCL_19") (pintype "bidirectional"))
      (node (ref "U6") (pin "6") (pinfunction "SCL_6") (pintype "input"))
    )
    (net (code "12") (name "/GSDA") (class "Default")
      (node (ref "R10") (pin "1") (pinfunction "1_1") (pintype "passive"))
      (node (ref "U3") (pin "18") (pinfunction "SDA_18") (pintype "bidirectional"))
      (node (ref "U6") (pin "5") (pinfunction "SDA_5") (pintype "bidirectional"))
    )
    (net (code "13") (name "/I2C_SCL") (class "Default")
      (node (ref "DISPLAY") (pin "2") (pinfunction "2_2") (pintype "passive"))
      (node (ref "U1") (pin "39") (pinfunction "IO22_39") (pintype "bidirectional"))
    )
    (net (code "14") (name "/I2C_SDA") (class "Default")
      (node (ref "DISPLAY") (pin "1") (pinfunction "1_1") (pintype "passive"))
      (node (ref "U1") (pin "42") (pinfunction "IO21_42") (pintype "bidirectional"))
    )
    (net (code "15") (name "/IO0") (class "Default")
      (node (ref "Q2") (pin "3") (pinfunction "C_3") (pintype "passive"))
      (node (ref "U1") (pin "23") (pinfunction "IO0_23") (pintype "bidirectional"))
    )
    (net (code "16") (name "/LCD_~{EN}") (class "Default")
      (node (ref "R22") (pin "1") (pinfunction "1_1") (pintype "passive"))
      (node (ref "U1") (pin "38") (pinfunction "IO19_38") (pintype "bidirectional"))
    )
    (net (code "17") (name "/PB1") (class "Default")
      (node (ref "R15") (pin "2") (pinfunction "2_2") (pintype "passive"))
      (node (ref "SW1") (pin "1") (pinfunction "1_1") (pintype "passive"))
      (node (ref "U1") (pin "8") (pinfunction "I39/SNS_VN_8") (pintype "input"))
    )
    (net (code "18") (name "/PB2") (class "Default")
      (node (ref "R16") (pin "2") (pinfunction "2_2") (pintype "passive"))
      (node (ref "SW2") (pin "2") (pinfunction "2_2") (pintype "passive"))
      (node (ref "U1") (pin "10") (pinfunction "I34/VDET_1_10") (pintype "input"))
    )
    (net (code "19") (name "/RTS") (class "Default")
      (node (ref "Q1") (pin "2") (pinfunction "E_2") (pintype "passive"))
      (node (ref "R20") (pin "2") (pinfunction "2_2") (pintype "passive"))
      (node (ref "U4") (pin "19") (pinfunction "~{RTS}_19") (pintype "output"))
    )
    (net (code "20") (name "/SA818_AIN") (class "Default")
      (node (ref "C1") (pin "1") (pinfunction "1_1") (pintype "passive"))
      (node (ref "R1") (pin "1") (pinfunction "1_1") (pintype "passive"))
      (node (ref "R3") (pin "2") (pinfunction "2_2") (pintype "passive"))
      (node (ref "U2") (pin "18") (pinfunction "MIC_IN_18") (pintype "passive"))
    )
    (net (code "21") (name "/SA818_AOUT") (class "Default")
      (node (ref "C2") (pin "2") (pinfunction "2_2") (pintype "passive"))
      (node (ref "U2") (pin "3") (pinfunction "AUDIO_OUT_3") (pintype "passive"))
    )
    (net (code "22") (name "/SA818_PD") (class "Default")
      (node (ref "U1") (pin "20") (pinfunction "IO13/MTCK_20") (pintype "bidirectional"))
      (node (ref "U2") (pin "6") (pinfunction "~{PD}_6") (pintype "passive"))
    )
    (net (code "23") (name "/SA818_RXD") (class "Default")
      (node (ref "U1") (pin "12") (pinfunction "IO32/32K_XP_12") (pintype "bidirectional"))
      (node (ref "U2") (pin "16") (pinfunction "RXD_16") (pintype "input"))
    )
    (net (code "24") (name "/SA818_RX{slash}~{TX}") (class "Default")
      (node (ref "U1") (pin "17") (pinfunction "IO14/MTMS_17") (pintype "bidirectional"))
      (node (ref "U2") (pin "5") (pinfunction "PTT_5") (pintype "passive"))
    )
    (net (code "25") (name "/SA818_TXD") (class "Default")
      (node (ref "U1") (pin "13") (pinfunction "IO33/32K_XN_13") (pintype "bidirectional"))
      (node (ref "U2") (pin "17") (pinfunction "TXD_17") (pintype "output"))
    )
    (net (code "26") (name "/U0RXD") (class "Default")
      (node (ref "U1") (pin "40") (pinfunction "U0RXD/IO3_40") (pintype "bidirectional"))
      (node (ref "U4") (pin "21") (pinfunction "TXD_21") (pintype "output"))
    )
    (net (code "27") (name "/U0TXD") (class "Default")
      (node (ref "U1") (pin "41") (pinfunction "U0TXD/IO1_41") (pintype "bidirectional"))
      (node (ref "U4") (pin "20") (pinfunction "RXD_20") (pintype "input"))
    )
    (net (code "28") (name "/USB_DN") (class "Default")
      (node (ref "D3") (pin "1") (pinfunction "K_1") (pintype "passive"))
      (node (ref "U4") (pin "4") (pinfunction "D-_4") (pintype "bidirectional"))
      (node (ref "USB") (pin "2") (pinfunction "D-_2") (pintype "passive"))
    )
    (net (code "29") (name "/USB_DP") (class "Default")
      (node (ref "D4") (pin "1") (pinfunction "K_1") (pintype "passive"))
      (node (ref "U4") (pin "3") (pinfunction "D+_3") (pintype "bidirectional"))
      (node (ref "USB") (pin "3") (pinfunction "D+_3") (pintype "passive"))
    )
    (net (code "30") (name "/USR_LED") (class "Default")
      (node (ref "U1") (pin "34") (pinfunction "IO5_34") (pintype "bidirectional"))
      (node (ref "USR") (pin "1") (pinfunction "A_1") (pintype "passive"))
    )
    (net (code "31") (name "GND") (class "Default")
      (node (ref "BATT") (pin "1") (pinfunction "1_1") (pintype "passive"))
      (node (ref "C10") (pin "1") (pinfunction "1_1") (pintype "passive"))
      (node (ref "C11") (pin "1") (pinfunction "1_1") (pintype "passive"))
      (node (ref "C12") (pin "1") (pinfunction "1_1") (pintype "passive"))
      (node (ref "C13") (pin "1") (pinfunction "1_1") (pintype "passive"))
      (node (ref "C14") (pin "1") (pinfunction "1_1") (pintype "passive"))
      (node (ref "C15") (pin "1") (pinfunction "1_1") (pintype "passive"))
      (node (ref "C16") (pin "1") (pinfunction "1_1") (pintype "passive"))
      (node (ref "C19") (pin "1") (pinfunction "1_1") (pintype "passive"))
      (node (ref "C20") (pin "1") (pinfunction "1_1") (pintype "passive"))
      (node (ref "C3") (pin "1") (pinfunction "1_1") (pintype "passive"))
      (node (ref "C4") (pin "1") (pinfunction "1_1") (pintype "passive"))
      (node (ref "C5") (pin "1") (pinfunction "1_1") (pintype "passive"))
      (node (ref "C6") (pin "1") (pinfunction "1_1") (pintype "passive"))
      (node (ref "C7") (pin "1") (pinfunction "1_1") (pintype "passive"))
      (node (ref "C9") (pin "1") (pinfunction "1_1") (pintype "passive"))
      (node (ref "D2") (pin "2") (pinfunction "A_2") (pintype "passive"))
      (node (ref "D3") (pin "2") (pinfunction "A_2") (pintype "passive"))
      (node (ref "D4") (pin "2") (pinfunction "A_2") (pintype "passive"))
      (node (ref "DISPLAY") (pin "4") (pinfunction "4_4") (pintype "passive"))
      (node (ref "GBAT") (pin "2") (pinfunction "-_2") (pintype "passive"))
      (node (ref "GPS") (pin "1") (pinfunction "1_1") (pintype "passive"))
      (node (ref "GPS") (pin "2") (pinfunction "2_2") (pintype "passive"))
      (node (ref "PWR_SW") (pin "3") (pinfunction "3_3") (pintype "passive"))
      (node (ref "R11") (pin "2") (pinfunction "2_2") (pintype "passive"))
      (node (ref "R15") (pin "1") (pinfunction "1_1") (pintype "passive"))
      (node (ref "R16") (pin "1") (pinfunction "1_1") (pintype "passive"))
      (node (ref "R19") (pin "2") (pinfunction "2_2") (pintype "passive"))
      (node (ref "R23") (pin "2") (pinfunction "2_2") (pintype "passive"))
      (node (ref "R3") (pin "1") (pinfunction "1_1") (pintype "passive"))
      (node (ref "R4") (pin "1") (pinfunction "1_1") (pintype "passive"))
      (node (ref "R5") (pin "2") (pinfunction "2_2") (pintype "passive"))
      (node (ref "R7") (pin "1") (pinfunction "1_1") (pintype "passive"))
      (node (ref "U1") (pin "49") (pinfunction "GND_49") (pintype "passive"))
      (node (ref "U2") (pin "10") (pinfunction "GND_10") (pintype "passive"))
      (node (ref "U2") (pin "9") (pinfunction "GND_9") (pintype "passive"))
      (node (ref "U3") (pin "10") (pinfunction "GND_10") (pintype "passive"))
      (node (ref "U3") (pin "12") (pinfunction "GND_12") (pintype "passive"))
      (node (ref "U3") (pin "13") (pinfunction "GND_13") (pintype "passive"))
      (node (ref "U3") (pin "24") (pinfunction "GND_24") (pintype "passive"))
      (node (ref "U3") (pin "4") (pinfunction "EXTI_4") (pintype "input"))
      (node (ref "U4") (pin "2") (pinfunction "GND_2") (pintype "power_in"))
      (node (ref "U4") (pin "25") (pinfunction "EP_25") (pintype "power_in"))
      (node (ref "U5") (pin "2") (pinfunction "VSS_2") (pintype "power_in"))
      (node (ref "U6") (pin "1") (pinfunction "A0_1") (pintype "input"))
      (node (ref "U6") (pin "2") (pinfunction "A1_2") (pintype "input"))
      (node (ref "U6") (pin "3") (pinfunction "A2_3") (pintype "input"))
      (node (ref "U6") (pin "4") (pinfunction "VSS_4") (pintype "power_in"))
      (node (ref "U6") (pin "7") (pinfunction "WP_7") (pintype "input"))
      (node (ref "U7") (pin "15") (pinfunction "PGND_15") (pintype "power_in"))
      (node (ref "U7") (pin "16") (pinfunction "PGND_16") (pintype "power_in"))
      (node (ref "U7") (pin "17") (pinfunction "EP_17") (pintype "power_in"))
      (node (ref "U7") (pin "5") (pinfunction "FB_5") (pintype "input"))
      (node (ref "U7") (pin "6") (pinfunction "AGND_6") (pintype "power_in"))
      (node (ref "U7") (pin "7") (pinfunction "FSW_7") (pintype "input"))
      (node (ref "U7") (pin "8") (pinfunction "DEF_8") (pintype "input"))
      (node (ref "USB") (pin "10") (pinfunction "SHLD5_10") (pintype "passive"))
      (node (ref "USB") (pin "11") (pinfunction "SHLD6_11") (pintype "passive"))
      (node (ref "USB") (pin "5") (pinfunction "GND_5") (pintype "passive"))
      (node (ref "USB") (pin "6") (pinfunction "SHLD1_6") (pintype "passive"))
      (node (ref "USB") (pin "7") (pinfunction "SHLD2_7") (pintype "passive"))
      (node (ref "USB") (pin "8") (pinfunction "SHLD3_8") (pintype "passive"))
      (node (ref "USB") (pin "9") (pinfunction "SHLD4_9") (pintype "passive"))
      (node (ref "VHF") (pin "2") (pinfunction "MNT_1_2") (pintype "passive"))
      (node (ref "VHF") (pin "3") (pinfunction "MNT_2_3") (pintype "passive"))
      (node (ref "VHF") (pin "4") (pinfunction "MNT_3_4") (pintype "passive"))
      (node (ref "VHF") (pin "5") (pinfunction "MNT_4_5") (pintype "passive"))
    )
    (net (code "32") (name "Net-(BLT-Feed_Point)") (class "Default")
      (node (ref "BLT") (pin "1") (pinfunction "Feed_Point_1") (pintype "passive"))
      (node (ref "U1") (pin "2") (pinfunction "LNA_IN_2") (pintype "passive"))
    )
    (net (code "33") (name "Net-(CHG-K)") (class "Default")
      (node (ref "CHG") (pin "2") (pinfunction "K_2") (pintype "passive"))
      (node (ref "R12") (pin "1") (pinfunction "1_1") (pintype "passive"))
    )
    (net (code "34") (name "Net-(D1-K)") (class "Default")
      (node (ref "D1") (pin "1") (pinfunction "K_1") (pintype "passive"))
      (node (ref "R8") (pin "2") (pinfunction "2_2") (pintype "passive"))
    )
    (net (code "35") (name "Net-(GBAT-+)") (class "Default")
      (node (ref "GBAT") (pin "1") (pinfunction "+_1") (pintype "passive"))
      (node (ref "R8") (pin "1") (pinfunction "1_1") (pintype "passive"))
      (node (ref "U3") (pin "22") (pinfunction "VBATT_22") (pintype "passive"))
    )
    (net (code "36") (name "Net-(L1-Pad1)") (class "Default")
      (node (ref "L1") (pin "1") (pinfunction "1_1") (pintype "passive"))
      (node (ref "U7") (pin "1") (pinfunction "SW_1") (pintype "power_in"))
      (node (ref "U7") (pin "2") (pinfunction "SW_2") (pintype "power_in"))
      (node (ref "U7") (pin "3") (pinfunction "SW_3") (pintype "power_in"))
    )
    (net (code "37") (name "Net-(L2-Pad2)") (class "Default")
      (node (ref "L2") (pin "2") (pinfunction "2_2") (pintype "passive"))
      (node (ref "R21") (pin "2") (pinfunction "2_2") (pintype "passive"))
    )
    (net (code "38") (name "Net-(Q1-B)") (class "Default")
      (node (ref "Q1") (pin "1") (pinfunction "B_1") (pintype "passive"))
      (node (ref "R17") (pin "1") (pinfunction "1_1") (pintype "passive"))
    )
    (net (code "39") (name "Net-(Q2-B)") (class "Default")
      (node (ref "Q2") (pin "1") (pinfunction "B_1") (pintype "passive"))
      (node (ref "R20") (pin "1") (pinfunction "1_1") (pintype "passive"))
    )
    (net (code "40") (name "Net-(Q3-DRAIN)") (class "Default")
      (node (ref "DISPLAY") (pin "3") (pinfunction "3_3") (pintype "passive"))
      (node (ref "Q3") (pin "3") (pinfunction "DRAIN_3") (pintype "passive"))
    )
    (net (code "41") (name "Net-(Q3-GATE)") (class "Default")
      (node (ref "Q3") (pin "1") (pinfunction "GATE_1") (pintype "passive"))
      (node (ref "R22") (pin "2") (pinfunction "2_2") (pintype "passive"))
    )
    (net (code "42") (name "Net-(R21-Pad1)") (class "Default")
      (node (ref "R21") (pin "1") (pinfunction "1_1") (pintype "passive"))
      (node (ref "U3") (pin "8") (pinfunction "VCC_RF_8") (pintype "passive"))
      (node (ref "U3") (pin "9") (pinfunction "VCC_RF_9") (pintype "output"))
    )
    (net (code "43") (name "Net-(U2-ANT)") (class "Default")
      (node (ref "U2") (pin "12") (pinfunction "ANT_12") (pintype "passive"))
      (node (ref "VHF") (pin "1") (pinfunction "1_1") (pintype "passive"))
    )
    (net (code "44") (name "Net-(U2-PWR_H{slash}~{L})") (class "Default")
      (node (ref "R5") (pin "1") (pinfunction "1_1") (pintype "passive"))
      (node (ref "U2") (pin "7") (pinfunction "PWR_H/~{L}_7") (pintype "passive"))
    )
    (net (code "45") (name "Net-(U3-RF_IN)") (class "Default")
      (node (ref "GPS") (pin "3") (pinfunction "3_3") (pintype "passive"))
      (node (ref "L2") (pin "1") (pinfunction "1_1") (pintype "passive"))
      (node (ref "U3") (pin "11") (pinfunction "RF_IN_11") (pintype "passive"))
    )
    (net (code "46") (name "Net-(U4-VBUS)") (class "Default")
      (node (ref "R18") (pin "2") (pinfunction "2_2") (pintype "passive"))
      (node (ref "R19") (pin "1") (pinfunction "1_1") (pintype "passive"))
      (node (ref "U4") (pin "8") (pinfunction "VBUS_8") (pintype "power_in"))
    )
    (net (code "47") (name "Net-(U4-~{RST})") (class "Default")
      (node (ref "R14") (pin "2") (pinfunction "2_2") (pintype "passive"))
      (node (ref "U4") (pin "9") (pinfunction "~{RST}_9") (pintype "input"))
    )
    (net (code "48") (name "Net-(U5-PROG)") (class "Default")
      (node (ref "R11") (pin "1") (pinfunction "1_1") (pintype "passive"))
      (node (ref "U5") (pin "5") (pinfunction "PROG_5") (pintype "passive"))
    )
    (net (code "49") (name "Net-(U5-STAT)") (class "Default")
      (node (ref "R12") (pin "2") (pinfunction "2_2") (pintype "passive"))
      (node (ref "U5") (pin "1") (pinfunction "STAT_1") (pintype "output"))
    )
    (net (code "50") (name "Net-(U7-EN)") (class "Default")
      (node (ref "PWR_SW") (pin "2") (pinfunction "2_2") (pintype "passive"))
      (node (ref "U7") (pin "13") (pinfunction "EN_13") (pintype "input"))
    )
    (net (code "51") (name "Net-(U7-SS{slash}TR)") (class "Default")
      (node (ref "C13") (pin "2") (pinfunction "2_2") (pintype "passive"))
      (node (ref "U7") (pin "9") (pinfunction "SS/TR_9") (pintype "input"))
    )
    (net (code "52") (name "Net-(USR-K)") (class "Default")
      (node (ref "R23") (pin "1") (pinfunction "1_1") (pintype "passive"))
      (node (ref "USR") (pin "2") (pinfunction "K_2") (pintype "passive"))
    )
    (net (code "53") (name "VBATT") (class "Default")
      (node (ref "BATT") (pin "2") (pinfunction "2_2") (pintype "passive"))
      (node (ref "Q4") (pin "3") (pinfunction "DRAIN_3") (pintype "passive"))
      (node (ref "U5") (pin "3") (pinfunction "VBAT_3") (pintype "power_in"))
    )
    (net (code "54") (name "VSNS") (class "Default")
      (node (ref "C14") (pin "2") (pinfunction "2_2") (pintype "passive"))
      (node (ref "C16") (pin "2") (pinfunction "2_2") (pintype "passive"))
      (node (ref "D5") (pin "1") (pinfunction "K_1") (pintype "passive"))
      (node (ref "PWR_SW") (pin "1") (pinfunction "1_1") (pintype "passive"))
      (node (ref "Q4") (pin "2") (pinfunction "SOURCE_2") (pintype "passive"))
      (node (ref "R2") (pin "2") (pinfunction "2_2") (pintype "passive"))
      (node (ref "U7") (pin "10") (pinfunction "AVIN_10") (pintype "power_in"))
      (node (ref "U7") (pin "11") (pinfunction "PVIN_11") (pintype "power_in"))
      (node (ref "U7") (pin "12") (pinfunction "PVIN_12") (pintype "power_in"))
    )
    (net (code "55") (name "unconnected-(BATT-PadMP1)") (class "Default")
      (node (ref "BATT") (pin "MP1") (pinfunction "MP1_MP1") (pintype "passive+no_connect"))
    )
    (net (code "56") (name "unconnected-(BATT-PadMP2)") (class "Default")
      (node (ref "BATT") (pin "MP2") (pinfunction "MP2_MP2") (pintype "passive+no_connect"))
    )
    (net (code "57") (name "unconnected-(BLT-NC-Pad2)") (class "Default")
      (node (ref "BLT") (pin "2") (pinfunction "NC_2") (pintype "passive"))
    )
    (net (code "58") (name "unconnected-(DISPLAY-MNT_1-Pad5)") (class "Default")
      (node (ref "DISPLAY") (pin "5") (pinfunction "MNT_1_5") (pintype "passive+no_connect"))
    )
    (net (code "59") (name "unconnected-(DISPLAY-MNT_2-Pad6)") (class "Default")
      (node (ref "DISPLAY") (pin "6") (pinfunction "MNT_2_6") (pintype "passive+no_connect"))
    )
    (net (code "60") (name "unconnected-(PWR_SW-PadMP1)") (class "Default")
      (node (ref "PWR_SW") (pin "MP1") (pinfunction "MP1_MP1") (pintype "passive+no_connect"))
    )
    (net (code "61") (name "unconnected-(PWR_SW-PadMP2)") (class "Default")
      (node (ref "PWR_SW") (pin "MP2") (pinfunction "MP2_MP2") (pintype "passive+no_connect"))
    )
    (net (code "62") (name "unconnected-(PWR_SW-PadMP3)") (class "Default")
      (node (ref "PWR_SW") (pin "MP3") (pinfunction "MP3_MP3") (pintype "passive+no_connect"))
    )
    (net (code "63") (name "unconnected-(PWR_SW-PadMP4)") (class "Default")
      (node (ref "PWR_SW") (pin "MP4") (pinfunction "MP4_MP4") (pintype "passive+no_connect"))
    )
    (net (code "64") (name "unconnected-(SW1-Pad2)") (class "Default")
      (node (ref "SW1") (pin "2") (pinfunction "2_2") (pintype "passive+no_connect"))
    )
    (net (code "65") (name "unconnected-(SW2-Pad1)") (class "Default")
      (node (ref "SW2") (pin "1") (pinfunction "1_1") (pintype "passive+no_connect"))
    )
    (net (code "66") (name "unconnected-(SW2-Pad3)") (class "Default")
      (node (ref "SW2") (pin "3") (pinfunction "3_3") (pintype "passive+no_connect"))
    )
    (net (code "67") (name "unconnected-(U1-CLK{slash}NC-Pad31)") (class "Default")
      (node (ref "U1") (pin "31") (pinfunction "CLK/NC_31") (pintype "passive+no_connect"))
    )
    (net (code "68") (name "unconnected-(U1-CMD{slash}NC-Pad30)") (class "Default")
      (node (ref "U1") (pin "30") (pinfunction "CMD/NC_30") (pintype "passive+no_connect"))
    )
    (net (code "69") (name "unconnected-(U1-I37{slash}SNS_CAPP-Pad6)") (class "Default")
      (node (ref "U1") (pin "6") (pinfunction "I37/SNS_CAPP_6") (pintype "input+no_connect"))
    )
    (net (code "70") (name "unconnected-(U1-I38{slash}SNS_CAPN-Pad7)") (class "Default")
      (node (ref "U1") (pin "7") (pinfunction "I38/SNS_CAPN_7") (pintype "input+no_connect"))
    )
    (net (code "71") (name "unconnected-(U1-IO2-Pad22)") (class "Default")
      (node (ref "U1") (pin "22") (pinfunction "IO2_22") (pintype "bidirectional+no_connect"))
    )
    (net (code "72") (name "unconnected-(U1-IO12{slash}MTDI-Pad18)") (class "Default")
      (node (ref "U1") (pin "18") (pinfunction "IO12/MTDI_18") (pintype "bidirectional+no_connect"))
    )
    (net (code "73") (name "unconnected-(U1-IO15{slash}MTDO-Pad21)") (class "Default")
      (node (ref "U1") (pin "21") (pinfunction "IO15/MTDO_21") (pintype "bidirectional+no_connect"))
    )
    (net (code "74") (name "unconnected-(U1-IO20-Pad27)") (class "Default")
      (node (ref "U1") (pin "27") (pinfunction "IO20_27") (pintype "bidirectional+no_connect"))
    )
    (net (code "75") (name "unconnected-(U1-NC-Pad25)") (class "Default")
      (node (ref "U1") (pin "25") (pinfunction "NC_25") (pintype "passive+no_connect"))
    )
    (net (code "76") (name "unconnected-(U1-NC-Pad35)") (class "Default")
      (node (ref "U1") (pin "35") (pinfunction "NC_35") (pintype "passive+no_connect"))
    )
    (net (code "77") (name "unconnected-(U1-NC-Pad36)") (class "Default")
      (node (ref "U1") (pin "36") (pinfunction "NC_36") (pintype "passive+no_connect"))
    )
    (net (code "78") (name "unconnected-(U1-NC-Pad44)") (class "Default")
      (node (ref "U1") (pin "44") (pinfunction "NC_44") (pintype "passive+no_connect"))
    )
    (net (code "79") (name "unconnected-(U1-NC-Pad45)") (class "Default")
      (node (ref "U1") (pin "45") (pinfunction "NC_45") (pintype "passive+no_connect"))
    )
    (net (code "80") (name "unconnected-(U1-NC-Pad47)") (class "Default")
      (node (ref "U1") (pin "47") (pinfunction "NC_47") (pintype "passive"))
    )
    (net (code "81") (name "unconnected-(U1-NC-Pad48)") (class "Default")
      (node (ref "U1") (pin "48") (pinfunction "NC_48") (pintype "passive+no_connect"))
    )
    (net (code "82") (name "unconnected-(U1-SD0{slash}IO7-Pad32)") (class "Default")
      (node (ref "U1") (pin "32") (pinfunction "SD0/IO7_32") (pintype "bidirectional+no_connect"))
    )
    (net (code "83") (name "unconnected-(U1-SD1{slash}IO8-Pad33)") (class "Default")
      (node (ref "U1") (pin "33") (pinfunction "SD1/IO8_33") (pintype "bidirectional+no_connect"))
    )
    (net (code "84") (name "unconnected-(U1-SD2{slash}IO9-Pad28)") (class "Default")
      (node (ref "U1") (pin "28") (pinfunction "SD2/IO9_28") (pintype "bidirectional+no_connect"))
    )
    (net (code "85") (name "unconnected-(U1-SD3{slash}IO10-Pad29)") (class "Default")
      (node (ref "U1") (pin "29") (pinfunction "SD3/IO10_29") (pintype "bidirectional+no_connect"))
    )
    (net (code "86") (name "unconnected-(U2-NC-Pad2)") (class "Default")
      (node (ref "U2") (pin "2") (pinfunction "NC_2") (pintype "passive+no_connect"))
    )
    (net (code "87") (name "unconnected-(U2-NC-Pad4)") (class "Default")
      (node (ref "U2") (pin "4") (pinfunction "NC_4") (pintype "passive+no_connect"))
    )
    (net (code "88") (name "unconnected-(U2-NC-Pad11)") (class "Default")
      (node (ref "U2") (pin "11") (pinfunction "NC_11") (pintype "passive+no_connect"))
    )
    (net (code "89") (name "unconnected-(U2-NC-Pad13)") (class "Default")
      (node (ref "U2") (pin "13") (pinfunction "NC_13") (pintype "passive+no_connect"))
    )
    (net (code "90") (name "unconnected-(U2-NC-Pad14)") (class "Default")
      (node (ref "U2") (pin "14") (pinfunction "NC_14") (pintype "passive+no_connect"))
    )
    (net (code "91") (name "unconnected-(U2-NC-Pad15)") (class "Default")
      (node (ref "U2") (pin "15") (pinfunction "NC_15") (pintype "passive+no_connect"))
    )
    (net (code "92") (name "unconnected-(U2-~{AUDIO_ON}-Pad1)") (class "Default")
      (node (ref "U2") (pin "1") (pinfunction "~{AUDIO_ON}_1") (pintype "output"))
    )
    (net (code "93") (name "unconnected-(U3-NC-Pad1)") (class "Default")
      (node (ref "U3") (pin "1") (pinfunction "NC_1") (pintype "passive+no_connect"))
    )
    (net (code "94") (name "unconnected-(U3-NC-Pad17)") (class "Default")
      (node (ref "U3") (pin "17") (pinfunction "NC_17") (pintype "passive+no_connect"))
    )
    (net (code "95") (name "unconnected-(U3-SPI_MISO{slash}CC1-Pad15)") (class "Default")
      (node (ref "U3") (pin "15") (pinfunction "SPI_MISO/CC1_15") (pintype "input+no_connect"))
    )
    (net (code "96") (name "unconnected-(U3-SPI_MOSI{slash}CC0-Pad14)") (class "Default")
      (node (ref "U3") (pin "14") (pinfunction "SPI_MOSI/CC0_14") (pintype "output+no_connect"))
    )
    (net (code "97") (name "unconnected-(U3-SPI_SCK{slash}CG0-Pad16)") (class "Default")
      (node (ref "U3") (pin "16") (pinfunction "SPI_SCK/CG0_16") (pintype "input+no_connect"))
    )
    (net (code "98") (name "unconnected-(U3-SPI_~{SS}-Pad2)") (class "Default")
      (node (ref "U3") (pin "2") (pinfunction "SPI_~{SS}_2") (pintype "input+no_connect"))
    )
    (net (code "99") (name "unconnected-(U3-USB_DM-Pad5)") (class "Default")
      (node (ref "U3") (pin "5") (pinfunction "USB_DM_5") (pintype "bidirectional+no_connect"))
    )
    (net (code "100") (name "unconnected-(U3-USB_DP-Pad6)") (class "Default")
      (node (ref "U3") (pin "6") (pinfunction "USB_DP_6") (pintype "bidirectional+no_connect"))
    )
    (net (code "101") (name "unconnected-(U3-VDDUSB-Pad7)") (class "Default")
      (node (ref "U3") (pin "7") (pinfunction "VDDUSB_7") (pintype "passive+no_connect"))
    )
    (net (code "102") (name "unconnected-(U4-GPIO.0{slash}TXT-Pad14)") (class "Default")
      (node (ref "U4") (pin "14") (pinfunction "GPIO.0/TXT_14") (pintype "bidirectional+no_connect"))
    )
    (net (code "103") (name "unconnected-(U4-GPIO.1{slash}RXT-Pad13)") (class "Default")
      (node (ref "U4") (pin "13") (pinfunction "GPIO.1/RXT_13") (pintype "bidirectional+no_connect"))
    )
    (net (code "104") (name "unconnected-(U4-GPIO.2{slash}RS485-Pad12)") (class "Default")
      (node (ref "U4") (pin "12") (pinfunction "GPIO.2/RS485_12") (pintype "bidirectional+no_connect"))
    )
    (net (code "105") (name "unconnected-(U4-GPIO.3{slash}WAKEUP-Pad11)") (class "Default")
      (node (ref "U4") (pin "11") (pinfunction "GPIO.3/WAKEUP_11") (pintype "bidirectional+no_connect"))
    )
    (net (code "106") (name "unconnected-(U4-NC-Pad10)") (class "Default")
      (node (ref "U4") (pin "10") (pinfunction "NC_10") (pintype "passive+no_connect"))
    )
    (net (code "107") (name "unconnected-(U4-NC-Pad16)") (class "Default")
      (node (ref "U4") (pin "16") (pinfunction "NC_16") (pintype "passive+no_connect"))
    )
    (net (code "108") (name "unconnected-(U4-SUSPEND-Pad17)") (class "Default")
      (node (ref "U4") (pin "17") (pinfunction "SUSPEND_17") (pintype "output+no_connect"))
    )
    (net (code "109") (name "unconnected-(U4-~{CTS}-Pad18)") (class "Default")
      (node (ref "U4") (pin "18") (pinfunction "~{CTS}_18") (pintype "input+no_connect"))
    )
    (net (code "110") (name "unconnected-(U4-~{DCD}-Pad24)") (class "Default")
      (node (ref "U4") (pin "24") (pinfunction "~{DCD}_24") (pintype "input+no_connect"))
    )
    (net (code "111") (name "unconnected-(U4-~{DSR}-Pad22)") (class "Default")
      (node (ref "U4") (pin "22") (pinfunction "~{DSR}_22") (pintype "input+no_connect"))
    )
    (net (code "112") (name "unconnected-(U4-~{RI}{slash}CLK-Pad1)") (class "Default")
      (node (ref "U4") (pin "1") (pinfunction "~{RI}/CLK_1") (pintype "bidirectional+no_connect"))
    )
    (net (code "113") (name "unconnected-(U4-~{SUSPEND}-Pad15)") (class "Default")
      (node (ref "U4") (pin "15") (pinfunction "~{SUSPEND}_15") (pintype "output+no_connect"))
    )
    (net (code "114") (name "unconnected-(U7-PG-Pad4)") (class "Default")
      (node (ref "U7") (pin "4") (pinfunction "PG_4") (pintype "tri_state+no_connect"))
    )
    (net (code "115") (name "unconnected-(USB-ID-Pad4)") (class "Default")
      (node (ref "USB") (pin "4") (pinfunction "ID_4") (pintype "passive+no_connect"))
    )
  )
)
